# 1-Schematic_onboard.net
KiCad netlist of a schematic drawn in EasyEDA
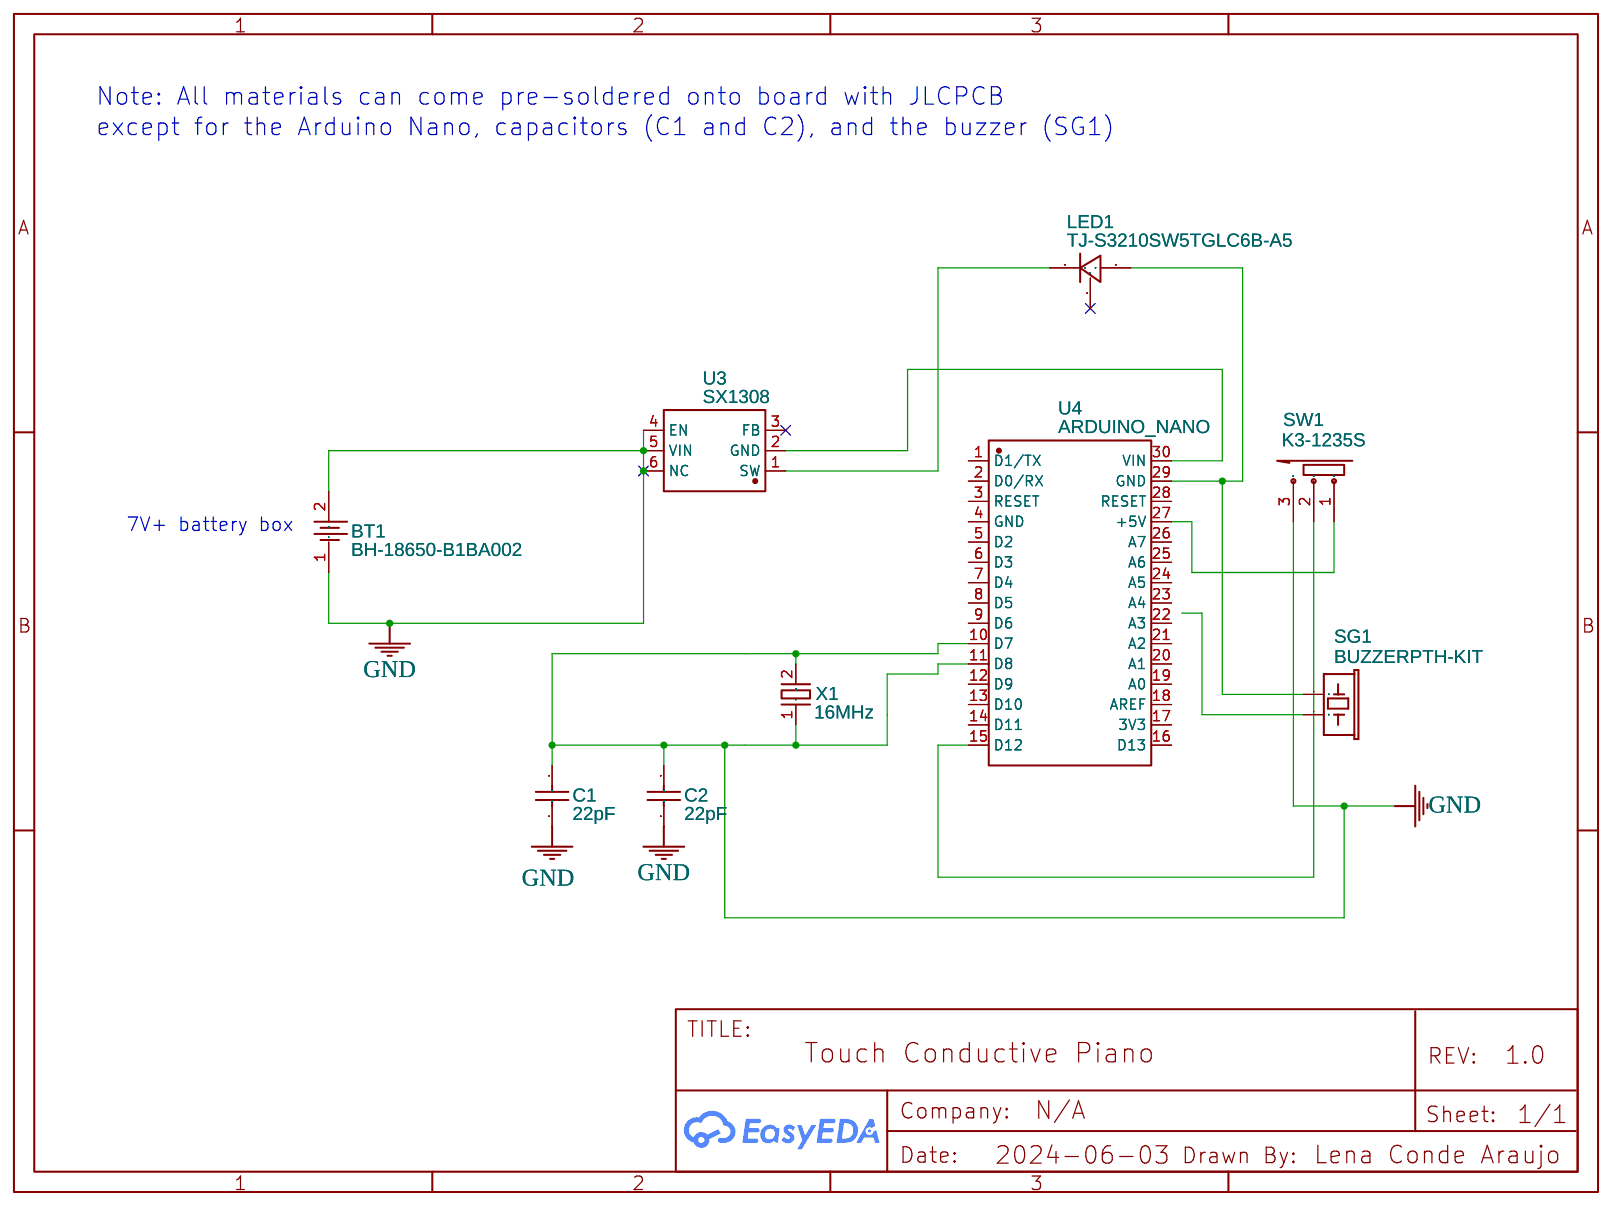
[diagram p0: schematic sheet]

(export (version "E")
  (design (tool "Eeschema 10.0.6"))
  (components
    (comp (ref "BT1")
      (value "BH-18650-B1BA002")
      (fields (field (name "Manufacturer") "MYOUNG(美阳)"))
      (libsource (lib "") (part "BH-18650-B1BA002"))
    )
    (comp (ref "C1") (value "22pF") (libsource (lib "") (part "COND_NONPOL_MKS_22uF")))
    (comp (ref "C2") (value "22pF") (libsource (lib "") (part "COND_NONPOL_MKS_22uF")))
    (comp (ref "LED1")
      (value "TJ-S3210SW5TGLC6B-A5")
      (fields (field (name "Manufacturer") "TOGIALED(统佳)"))
      (libsource (lib "") (part "TJ-S3210SW5TGLC6B-A5"))
    )
    (comp (ref "SG1") (value "BUZZERPTH-KIT") (libsource (lib "") (part "BUZZERPTH-KIT")))
    (comp (ref "SW1")
      (value "K3-1235S")
      (fields (field (name "Manufacturer Part") "K3-1235S-F1") (field (name "Manufacturer") "韩国韩荣"))
      (libsource (lib "") (part "K3-1235S"))
    )
    (comp (ref "U3")
      (value "SX1308")
      (fields (field (name "Manufacturer") "SX(硕芯科技)"))
      (libsource (lib "") (part "SX1308"))
    )
    (comp (ref "U4") (value "ARDUINO_NANO") (libsource (lib "") (part "ARDUINO_NANO")))
    (comp (ref "X1")
      (value "16MHz")
      (fields (field (name "Manufacturer Part") "KMS160001210") (field (name "Manufacturer") "KYX(凯越翔)"))
      (libsource (lib "") (part "KMS160001210"))
    )
  )
  (nets
    (net (code "1") (name "GND") (class "Default")
      (node (ref "BT1") (pin "1") (pinfunction "1_1") (pintype "input"))
      (node (ref "BT1") (pin "2") (pinfunction "2_2") (pintype "input"))
      (node (ref "C1") (pin "1") (pinfunction "1_1") (pintype "unspecified"))
      (node (ref "C1") (pin "2") (pinfunction "2_2") (pintype "unspecified"))
      (node (ref "C2") (pin "1") (pinfunction "1_1") (pintype "unspecified"))
      (node (ref "C2") (pin "2") (pinfunction "2_2") (pintype "unspecified"))
      (node (ref "SW1") (pin "3") (pinfunction "3_3") (pintype "unspecified"))
      (node (ref "U3") (pin "4") (pinfunction "EN_4") (pintype "unspecified"))
      (node (ref "U3") (pin "5") (pinfunction "VIN_5") (pintype "unspecified"))
      (node (ref "U3") (pin "6") (pinfunction "NC_6") (pintype "unspecified"))
      (node (ref "U4") (pin "10") (pinfunction "D7_10") (pintype "unspecified"))
      (node (ref "U4") (pin "11") (pinfunction "D8_11") (pintype "unspecified"))
      (node (ref "X1") (pin "1") (pinfunction "1_1") (pintype "input"))
      (node (ref "X1") (pin "2") (pinfunction "GND_2") (pintype "input"))
    )
    (net (code "2") (name "Net-(SG1-1)") (class "Default")
      (node (ref "LED1") (pin "2") (pinfunction "2_2") (pintype "unspecified"))
      (node (ref "SG1") (pin "+") (pinfunction "1_+") (pintype "unspecified"))
      (node (ref "U4") (pin "29") (pinfunction "GND_29") (pintype "unspecified"))
    )
    (net (code "3") (name "Net-(U3-GND)") (class "Default")
      (node (ref "U3") (pin "2") (pinfunction "GND_2") (pintype "unspecified"))
      (node (ref "U4") (pin "30") (pinfunction "VIN_30") (pintype "unspecified"))
    )
    (net (code "4") (name "Net-(U3-SW)") (class "Default")
      (node (ref "LED1") (pin "1") (pinfunction "1_1") (pintype "unspecified"))
      (node (ref "U3") (pin "1") (pinfunction "SW_1") (pintype "unspecified"))
    )
    (net (code "5") (name "Net-(U4-+5V)") (class "Default")
      (node (ref "SW1") (pin "1") (pinfunction "1_1") (pintype "unspecified"))
      (node (ref "U4") (pin "27") (pinfunction "+5V_27") (pintype "unspecified"))
    )
    (net (code "6") (name "Net-(U4-D12)") (class "Default")
      (node (ref "SW1") (pin "2") (pinfunction "2_2") (pintype "unspecified"))
      (node (ref "U4") (pin "15") (pinfunction "D12_15") (pintype "unspecified"))
    )
    (net (code "7") (name "unconnected-(LED1-Pad3)") (class "Default")
      (node (ref "LED1") (pin "3") (pinfunction "3_3") (pintype "unspecified+no_connect"))
    )
    (net (code "8") (name "unconnected-(SG1-2-Pad-)") (class "Default")
      (node (ref "SG1") (pin "-") (pinfunction "2_-") (pintype "unspecified"))
    )
    (net (code "9") (name "unconnected-(U3-FB-Pad3)") (class "Default")
      (node (ref "U3") (pin "3") (pinfunction "FB_3") (pintype "unspecified+no_connect"))
    )
    (net (code "10") (name "unconnected-(U4-3V3-Pad17)") (class "Default")
      (node (ref "U4") (pin "17") (pinfunction "3V3_17") (pintype "unspecified"))
    )
    (net (code "11") (name "unconnected-(U4-A0-Pad19)") (class "Default")
      (node (ref "U4") (pin "19") (pinfunction "A0_19") (pintype "unspecified"))
    )
    (net (code "12") (name "unconnected-(U4-A1-Pad20)") (class "Default")
      (node (ref "U4") (pin "20") (pinfunction "A1_20") (pintype "unspecified"))
    )
    (net (code "13") (name "unconnected-(U4-A2-Pad21)") (class "Default")
      (node (ref "U4") (pin "21") (pinfunction "A2_21") (pintype "unspecified"))
    )
    (net (code "14") (name "unconnected-(U4-A3-Pad22)") (class "Default")
      (node (ref "U4") (pin "22") (pinfunction "A3_22") (pintype "unspecified"))
    )
    (net (code "15") (name "unconnected-(U4-A4-Pad23)") (class "Default")
      (node (ref "U4") (pin "23") (pinfunction "A4_23") (pintype "unspecified"))
    )
    (net (code "16") (name "unconnected-(U4-A5-Pad24)") (class "Default")
      (node (ref "U4") (pin "24") (pinfunction "A5_24") (pintype "unspecified"))
    )
    (net (code "17") (name "unconnected-(U4-A6-Pad25)") (class "Default")
      (node (ref "U4") (pin "25") (pinfunction "A6_25") (pintype "unspecified"))
    )
    (net (code "18") (name "unconnected-(U4-A7-Pad26)") (class "Default")
      (node (ref "U4") (pin "26") (pinfunction "A7_26") (pintype "unspecified"))
    )
    (net (code "19") (name "unconnected-(U4-AREF-Pad18)") (class "Default")
      (node (ref "U4") (pin "18") (pinfunction "AREF_18") (pintype "unspecified"))
    )
    (net (code "20") (name "unconnected-(U4-D0{slash}RX-Pad2)") (class "Default")
      (node (ref "U4") (pin "2") (pinfunction "D0/RX_2") (pintype "unspecified"))
    )
    (net (code "21") (name "unconnected-(U4-D1{slash}TX-Pad1)") (class "Default")
      (node (ref "U4") (pin "1") (pinfunction "D1/TX_1") (pintype "unspecified"))
    )
    (net (code "22") (name "unconnected-(U4-D2-Pad5)") (class "Default")
      (node (ref "U4") (pin "5") (pinfunction "D2_5") (pintype "unspecified"))
    )
    (net (code "23") (name "unconnected-(U4-D3-Pad6)") (class "Default")
      (node (ref "U4") (pin "6") (pinfunction "D3_6") (pintype "unspecified"))
    )
    (net (code "24") (name "unconnected-(U4-D4-Pad7)") (class "Default")
      (node (ref "U4") (pin "7") (pinfunction "D4_7") (pintype "unspecified"))
    )
    (net (code "25") (name "unconnected-(U4-D5-Pad8)") (class "Default")
      (node (ref "U4") (pin "8") (pinfunction "D5_8") (pintype "unspecified"))
    )
    (net (code "26") (name "unconnected-(U4-D6-Pad9)") (class "Default")
      (node (ref "U4") (pin "9") (pinfunction "D6_9") (pintype "unspecified"))
    )
    (net (code "27") (name "unconnected-(U4-D9-Pad12)") (class "Default")
      (node (ref "U4") (pin "12") (pinfunction "D9_12") (pintype "unspecified"))
    )
    (net (code "28") (name "unconnected-(U4-D10-Pad13)") (class "Default")
      (node (ref "U4") (pin "13") (pinfunction "D10_13") (pintype "unspecified"))
    )
    (net (code "29") (name "unconnected-(U4-D11-Pad14)") (class "Default")
      (node (ref "U4") (pin "14") (pinfunction "D11_14") (pintype "unspecified"))
    )
    (net (code "30") (name "unconnected-(U4-D13-Pad16)") (class "Default")
      (node (ref "U4") (pin "16") (pinfunction "D13_16") (pintype "unspecified"))
    )
    (net (code "31") (name "unconnected-(U4-GND-Pad4)") (class "Default")
      (node (ref "U4") (pin "4") (pinfunction "GND_4") (pintype "unspecified"))
    )
    (net (code "32") (name "unconnected-(U4-RESET-Pad3)") (class "Default")
      (node (ref "U4") (pin "3") (pinfunction "RESET_3") (pintype "unspecified"))
    )
    (net (code "33") (name "unconnected-(U4-RESET-Pad28)") (class "Default")
      (node (ref "U4") (pin "28") (pinfunction "RESET_28") (pintype "unspecified"))
    )
  )
)
